# FLYBACK_SWITCHING_POWER_SUPPLY_V1_1.net
KiCad netlist of a schematic drawn in Altium Designer
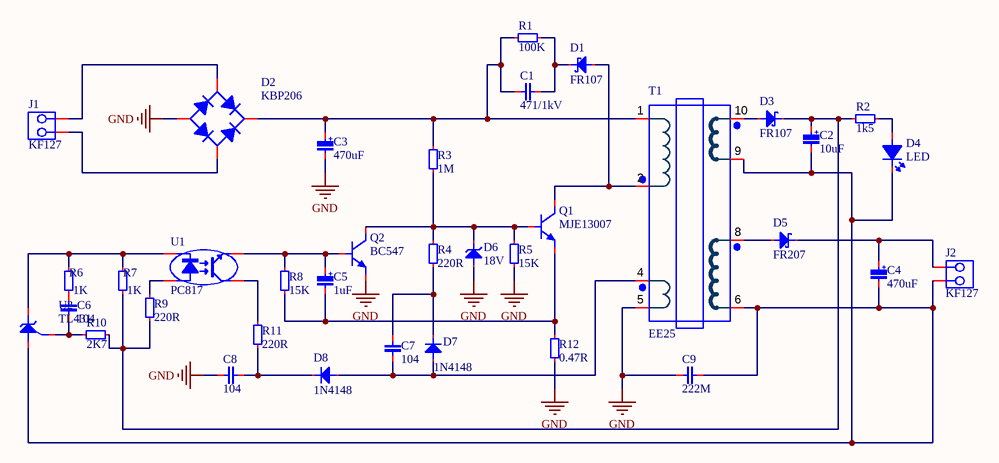
[diagram p0: FLYBACK_SWITCHING_POWER_SUPPLY_V1_1.SchDoc]

(export (version "E")
  (design (tool "Eeschema 10.0.6"))
  (components
    (comp (ref "C1")
      (value "471/1kV")
      (footprint "CAP_Ceramic_5MM")
      (libsource (lib "MyAltiumLibrary") (part "Capacitors(Disc)"))
    )
    (comp (ref "C2")
      (value "10uF")
      (footprint "CAP_RAD_D05x11")
      (libsource (lib "MyAltiumLibrary") (part "Capacitor(Radian)"))
    )
    (comp (ref "C3")
      (value "470uF")
      (footprint "CAP_RAD_D10x12.5")
      (libsource (lib "MyAltiumLibrary") (part "Capacitor(Radian)"))
    )
    (comp (ref "C4")
      (value "470uF")
      (footprint "CAP_RAD_D10x12.5")
      (libsource (lib "MyAltiumLibrary") (part "Capacitor(Radian)"))
    )
    (comp (ref "C5")
      (value "1uF")
      (footprint "CAP_RAD_D05x11")
      (libsource (lib "MyAltiumLibrary") (part "Capacitor(Radian)"))
    )
    (comp (ref "C6")
      (value "104")
      (footprint "CAP_Ceramic_2.5MM")
      (libsource (lib "") (part "Capacitors(Disc)_2"))
    )
    (comp (ref "C7")
      (value "104")
      (footprint "CAP_Ceramic_2.5MM")
      (libsource (lib "") (part "Capacitors(Disc)_1"))
    )
    (comp (ref "C8")
      (value "104")
      (footprint "CAP_Ceramic_2.5MM")
      (libsource (lib "MyAltiumLibrary") (part "Capacitors(Disc)"))
    )
    (comp (ref "C9")
      (value "222M")
      (footprint "CAP_Ceramic_473M_9.65mm")
      (libsource (lib "MyAltiumLibrary") (part "Capacitors(Disc)"))
    )
    (comp (ref "D1")
      (value "FR107")
      (footprint "DO-204AL-BK")
      (description "1A 1000V")
      (libsource (lib "MyAltiumLibrary") (part "Diode-FR107"))
    )
    (comp (ref "D2")
      (value "KBP206")
      (footprint "DIODE-KBP206")
      (libsource (lib "MyAltiumLibrary") (part "Diode-KBP206"))
    )
    (comp (ref "D3")
      (value "FR107")
      (footprint "DO-204AL-BK")
      (description "1A 1000V")
      (libsource (lib "MyAltiumLibrary") (part "Diode-FR107"))
    )
    (comp (ref "D4") (value "LED") (footprint "LED_5MM") (libsource (lib "MyAltiumLibrary") (part "LED 5MM")))
    (comp (ref "D5")
      (value "FR207")
      (footprint "DO-204AC-BK")
      (libsource (lib "MyAltiumLibrary") (part "Diode-FR207"))
    )
    (comp (ref "D6")
      (value "18V")
      (footprint "DO-204AL-RD")
      (libsource (lib "MyAltiumLibrary") (part "Diode-Zener"))
    )
    (comp (ref "D7")
      (value "1N4148")
      (footprint "DO-204AH-RD")
      (description "The fast switching diode")
      (libsource (lib "MyAltiumLibrary") (part "Diode-1N4148"))
    )
    (comp (ref "D8")
      (value "1N4148")
      (footprint "DO-204AH-RD")
      (description "The fast switching diode")
      (libsource (lib "MyAltiumLibrary") (part "Diode-1N4148"))
    )
    (comp (ref "J1")
      (value "KF127")
      (footprint "DG127-5.0-02P-14-00AH")
      (libsource (lib "MyAltiumLibrary") (part "DG127-5.0-02P-14-00AH"))
    )
    (comp (ref "J2")
      (value "KF127")
      (footprint "DG127-5.0-02P-14-00AH")
      (libsource (lib "") (part "DG127-5.0-02P-14-00AH_1"))
    )
    (comp (ref "Q1")
      (value "MJE13007")
      (footprint "TO-220-HEAT-SINK-1")
      (libsource (lib "MyAltiumLibrary") (part "Transistor-MJE13007"))
    )
    (comp (ref "Q2")
      (value "BC547")
      (footprint "TO-92")
      (description "VCEO: 45 Vdc\r\nVCBO: 50 Vdc\r\nVEBO: 6.0 Vdc")
      (libsource (lib "MyAltiumLibrary") (part "Transistor-BC547"))
    )
    (comp (ref "R1")
      (value "100K")
      (footprint "RES-0.5W-H")
      (libsource (lib "MyAltiumLibrary") (part "Resistors THD"))
    )
    (comp (ref "R2")
      (value "1k5")
      (footprint "RES-0.25W-H")
      (libsource (lib "MyAltiumLibrary") (part "Resistors THD"))
    )
    (comp (ref "R3") (value "1M") (footprint "RES-1W-V") (libsource (lib "") (part "Resistors THD_1")))
    (comp (ref "R4") (value "220R") (footprint "RES-0.25W-H") (libsource (lib "") (part "Resistors THD_1")))
    (comp (ref "R5") (value "15K") (footprint "RES-0.25W-H") (libsource (lib "") (part "Resistors THD_1")))
    (comp (ref "R6") (value "1K") (footprint "RES-0.25W-H") (libsource (lib "") (part "Resistors THD_1")))
    (comp (ref "R7") (value "1K") (footprint "RES-0.25W-H") (libsource (lib "") (part "Resistors THD_1")))
    (comp (ref "R8") (value "15K") (footprint "RES-0.25W-H") (libsource (lib "") (part "Resistors THD_1")))
    (comp (ref "R9") (value "220R") (footprint "RES-0.25W-H") (libsource (lib "") (part "Resistors THD_1")))
    (comp (ref "R10")
      (value "2K7")
      (footprint "RES-0.25W-H")
      (libsource (lib "MyAltiumLibrary") (part "Resistors THD"))
    )
    (comp (ref "R11") (value "220R") (footprint "RES-0.25W-H") (libsource (lib "") (part "Resistors THD_1")))
    (comp (ref "R12") (value "0.47R") (footprint "RES-1W-V") (libsource (lib "") (part "Resistors THD_1")))
    (comp (ref "T1")
      (value "EE25")
      (footprint "TRANSFORMER-EE25-10-6-VERTICAL(5+5)")
      (libsource (lib "MyAltiumLibrary") (part "TRANS-EE25-10-6-VERTICAL(5+5)"))
    )
    (comp (ref "U1")
      (value "PC817")
      (footprint "PC817-DIP")
      (libsource (lib "MyAltiumLibrary") (part "Opto-PC817"))
    )
    (comp (ref "U2")
      (value "TL431")
      (footprint "TO-92")
      (libsource (lib "MyAltiumLibrary") (part "Ic-TL431"))
    )
  )
  (nets
    (net (code "1") (name "GND") (class "Default")
      (node (ref "C3") (pin "2") (pinfunction "2_2") (pintype "passive"))
      (node (ref "C8") (pin "2") (pinfunction "2_2") (pintype "passive"))
      (node (ref "C9") (pin "2") (pinfunction "2_2") (pintype "passive"))
      (node (ref "D2") (pin "4") (pinfunction "-_4") (pintype "passive"))
      (node (ref "D6") (pin "1") (pinfunction "1_1") (pintype "passive"))
      (node (ref "Q2") (pin "3") (pinfunction "E_3") (pintype "passive"))
      (node (ref "R12") (pin "1") (pinfunction "1_1") (pintype "passive"))
      (node (ref "R5") (pin "1") (pinfunction "1_1") (pintype "passive"))
      (node (ref "T1") (pin "5") (pinfunction "6_5") (pintype "passive"))
    )
    (net (code "2") (name "Net-(C1-Pad1)") (class "Default")
      (node (ref "C1") (pin "1") (pinfunction "1_1") (pintype "passive"))
      (node (ref "D1") (pin "2") (pinfunction "2_2") (pintype "passive"))
      (node (ref "R1") (pin "1") (pinfunction "1_1") (pintype "passive"))
    )
    (net (code "3") (name "Net-(C2-Pad1)") (class "Default")
      (node (ref "C2") (pin "1") (pinfunction "1_1") (pintype "passive"))
      (node (ref "D3") (pin "2") (pinfunction "2_2") (pintype "passive"))
      (node (ref "R10") (pin "1") (pinfunction "1_1") (pintype "passive"))
      (node (ref "R2") (pin "2") (pinfunction "2_2") (pintype "passive"))
      (node (ref "R7") (pin "1") (pinfunction "1_1") (pintype "passive"))
      (node (ref "R9") (pin "1") (pinfunction "1_1") (pintype "passive"))
    )
    (net (code "4") (name "Net-(C4-Pad1)") (class "Default")
      (node (ref "C4") (pin "1") (pinfunction "1_1") (pintype "passive"))
      (node (ref "D5") (pin "2") (pinfunction "2_2") (pintype "passive"))
      (node (ref "J2") (pin "2") (pinfunction "2_2") (pintype "passive"))
    )
    (net (code "5") (name "Net-(C6-Pad1)") (class "Default")
      (node (ref "C6") (pin "1") (pinfunction "1_1") (pintype "passive"))
      (node (ref "R6") (pin "1") (pinfunction "1_1") (pintype "passive"))
    )
    (net (code "6") (name "Net-(C6-Pad2)") (class "Default")
      (node (ref "C6") (pin "2") (pinfunction "2_2") (pintype "passive"))
      (node (ref "R10") (pin "2") (pinfunction "2_2") (pintype "passive"))
      (node (ref "U2") (pin "1") (pinfunction "1_1") (pintype "passive"))
    )
    (net (code "7") (name "Net-(C7-Pad1)") (class "Default")
      (node (ref "C7") (pin "1") (pinfunction "1_1") (pintype "passive"))
      (node (ref "D7") (pin "1") (pinfunction "1_1") (pintype "passive"))
      (node (ref "D8") (pin "1") (pinfunction "1_1") (pintype "passive"))
      (node (ref "T1") (pin "4") (pinfunction "4_4") (pintype "passive"))
    )
    (net (code "8") (name "Net-(C7-Pad2)") (class "Default")
      (node (ref "C7") (pin "2") (pinfunction "2_2") (pintype "passive"))
      (node (ref "D7") (pin "2") (pinfunction "2_2") (pintype "passive"))
      (node (ref "R4") (pin "1") (pinfunction "1_1") (pintype "passive"))
    )
    (net (code "9") (name "Net-(C8-Pad1)") (class "Default")
      (node (ref "C8") (pin "1") (pinfunction "1_1") (pintype "passive"))
      (node (ref "D8") (pin "2") (pinfunction "2_2") (pintype "passive"))
      (node (ref "R11") (pin "1") (pinfunction "1_1") (pintype "passive"))
    )
    (net (code "10") (name "Net-(D2-+)") (class "Default")
      (node (ref "C1") (pin "2") (pinfunction "2_2") (pintype "passive"))
      (node (ref "C3") (pin "1") (pinfunction "1_1") (pintype "passive"))
      (node (ref "D2") (pin "1") (pinfunction "+_1") (pintype "passive"))
      (node (ref "R1") (pin "2") (pinfunction "2_2") (pintype "passive"))
      (node (ref "R3") (pin "2") (pinfunction "2_2") (pintype "passive"))
      (node (ref "T1") (pin "1") (pinfunction "1_1") (pintype "passive"))
    )
    (net (code "11") (name "Net-(D2-AC-Pad2)") (class "Default")
      (node (ref "D2") (pin "2") (pinfunction "AC_2") (pintype "passive"))
      (node (ref "J1") (pin "1") (pinfunction "1_1") (pintype "passive"))
    )
    (net (code "12") (name "Net-(D2-AC-Pad3)") (class "Default")
      (node (ref "D2") (pin "3") (pinfunction "AC_3") (pintype "passive"))
      (node (ref "J1") (pin "2") (pinfunction "2_2") (pintype "passive"))
    )
    (net (code "13") (name "Net-(D3-Pad1)") (class "Default")
      (node (ref "D3") (pin "1") (pinfunction "1_1") (pintype "passive"))
      (node (ref "T1") (pin "10") (pinfunction "10_10") (pintype "passive"))
    )
    (net (code "14") (name "Net-(D4-A)") (class "Default")
      (node (ref "D4") (pin "1") (pinfunction "A_1") (pintype "passive"))
      (node (ref "R2") (pin "1") (pinfunction "1_1") (pintype "passive"))
    )
    (net (code "15") (name "Net-(D4-K)") (class "Default")
      (node (ref "C2") (pin "2") (pinfunction "2_2") (pintype "passive"))
      (node (ref "C4") (pin "2") (pinfunction "2_2") (pintype "passive"))
      (node (ref "C9") (pin "1") (pinfunction "1_1") (pintype "passive"))
      (node (ref "D4") (pin "2") (pinfunction "K_2") (pintype "passive"))
      (node (ref "J2") (pin "1") (pinfunction "1_1") (pintype "passive"))
      (node (ref "T1") (pin "6") (pinfunction "6_6") (pintype "passive"))
      (node (ref "T1") (pin "9") (pinfunction "9_9") (pintype "passive"))
      (node (ref "U2") (pin "2") (pinfunction "2_2") (pintype "passive"))
    )
    (net (code "16") (name "Net-(D5-Pad1)") (class "Default")
      (node (ref "D5") (pin "1") (pinfunction "1_1") (pintype "passive"))
      (node (ref "T1") (pin "8") (pinfunction "8_8") (pintype "passive"))
    )
    (net (code "17") (name "Net-(Q1-B)") (class "Default")
      (node (ref "D6") (pin "2") (pinfunction "2_2") (pintype "passive"))
      (node (ref "Q1") (pin "1") (pinfunction "B_1") (pintype "passive"))
      (node (ref "Q2") (pin "1") (pinfunction "C_1") (pintype "passive"))
      (node (ref "R3") (pin "1") (pinfunction "1_1") (pintype "passive"))
      (node (ref "R4") (pin "2") (pinfunction "2_2") (pintype "passive"))
      (node (ref "R5") (pin "2") (pinfunction "2_2") (pintype "passive"))
    )
    (net (code "18") (name "Net-(Q1-C)") (class "Default")
      (node (ref "D1") (pin "1") (pinfunction "1_1") (pintype "passive"))
      (node (ref "Q1") (pin "2") (pinfunction "C_2") (pintype "passive"))
      (node (ref "T1") (pin "2") (pinfunction "2_2") (pintype "passive"))
    )
    (net (code "19") (name "Net-(Q1-E)") (class "Default")
      (node (ref "C5") (pin "2") (pinfunction "2_2") (pintype "passive"))
      (node (ref "Q1") (pin "3") (pinfunction "E_3") (pintype "passive"))
      (node (ref "R12") (pin "2") (pinfunction "2_2") (pintype "passive"))
      (node (ref "R8") (pin "1") (pinfunction "1_1") (pintype "passive"))
    )
    (net (code "20") (name "Net-(Q2-B)") (class "Default")
      (node (ref "C5") (pin "1") (pinfunction "1_1") (pintype "passive"))
      (node (ref "Q2") (pin "2") (pinfunction "B_2") (pintype "passive"))
      (node (ref "R8") (pin "2") (pinfunction "2_2") (pintype "passive"))
      (node (ref "U1") (pin "3") (pinfunction "E_3") (pintype "passive"))
    )
    (net (code "21") (name "Net-(U1-A)") (class "Default")
      (node (ref "R9") (pin "2") (pinfunction "2_2") (pintype "passive"))
      (node (ref "U1") (pin "1") (pinfunction "A_1") (pintype "passive"))
    )
    (net (code "22") (name "Net-(U1-C)") (class "Default")
      (node (ref "R11") (pin "2") (pinfunction "2_2") (pintype "passive"))
      (node (ref "U1") (pin "4") (pinfunction "C_4") (pintype "passive"))
    )
    (net (code "23") (name "Net-(U1-K)") (class "Default")
      (node (ref "R6") (pin "2") (pinfunction "2_2") (pintype "passive"))
      (node (ref "R7") (pin "2") (pinfunction "2_2") (pintype "passive"))
      (node (ref "U1") (pin "2") (pinfunction "K_2") (pintype "passive"))
      (node (ref "U2") (pin "3") (pinfunction "3_3") (pintype "passive"))
    )
  )
)
